# CPLD.net
KiCad netlist of a schematic drawn in Altium Designer
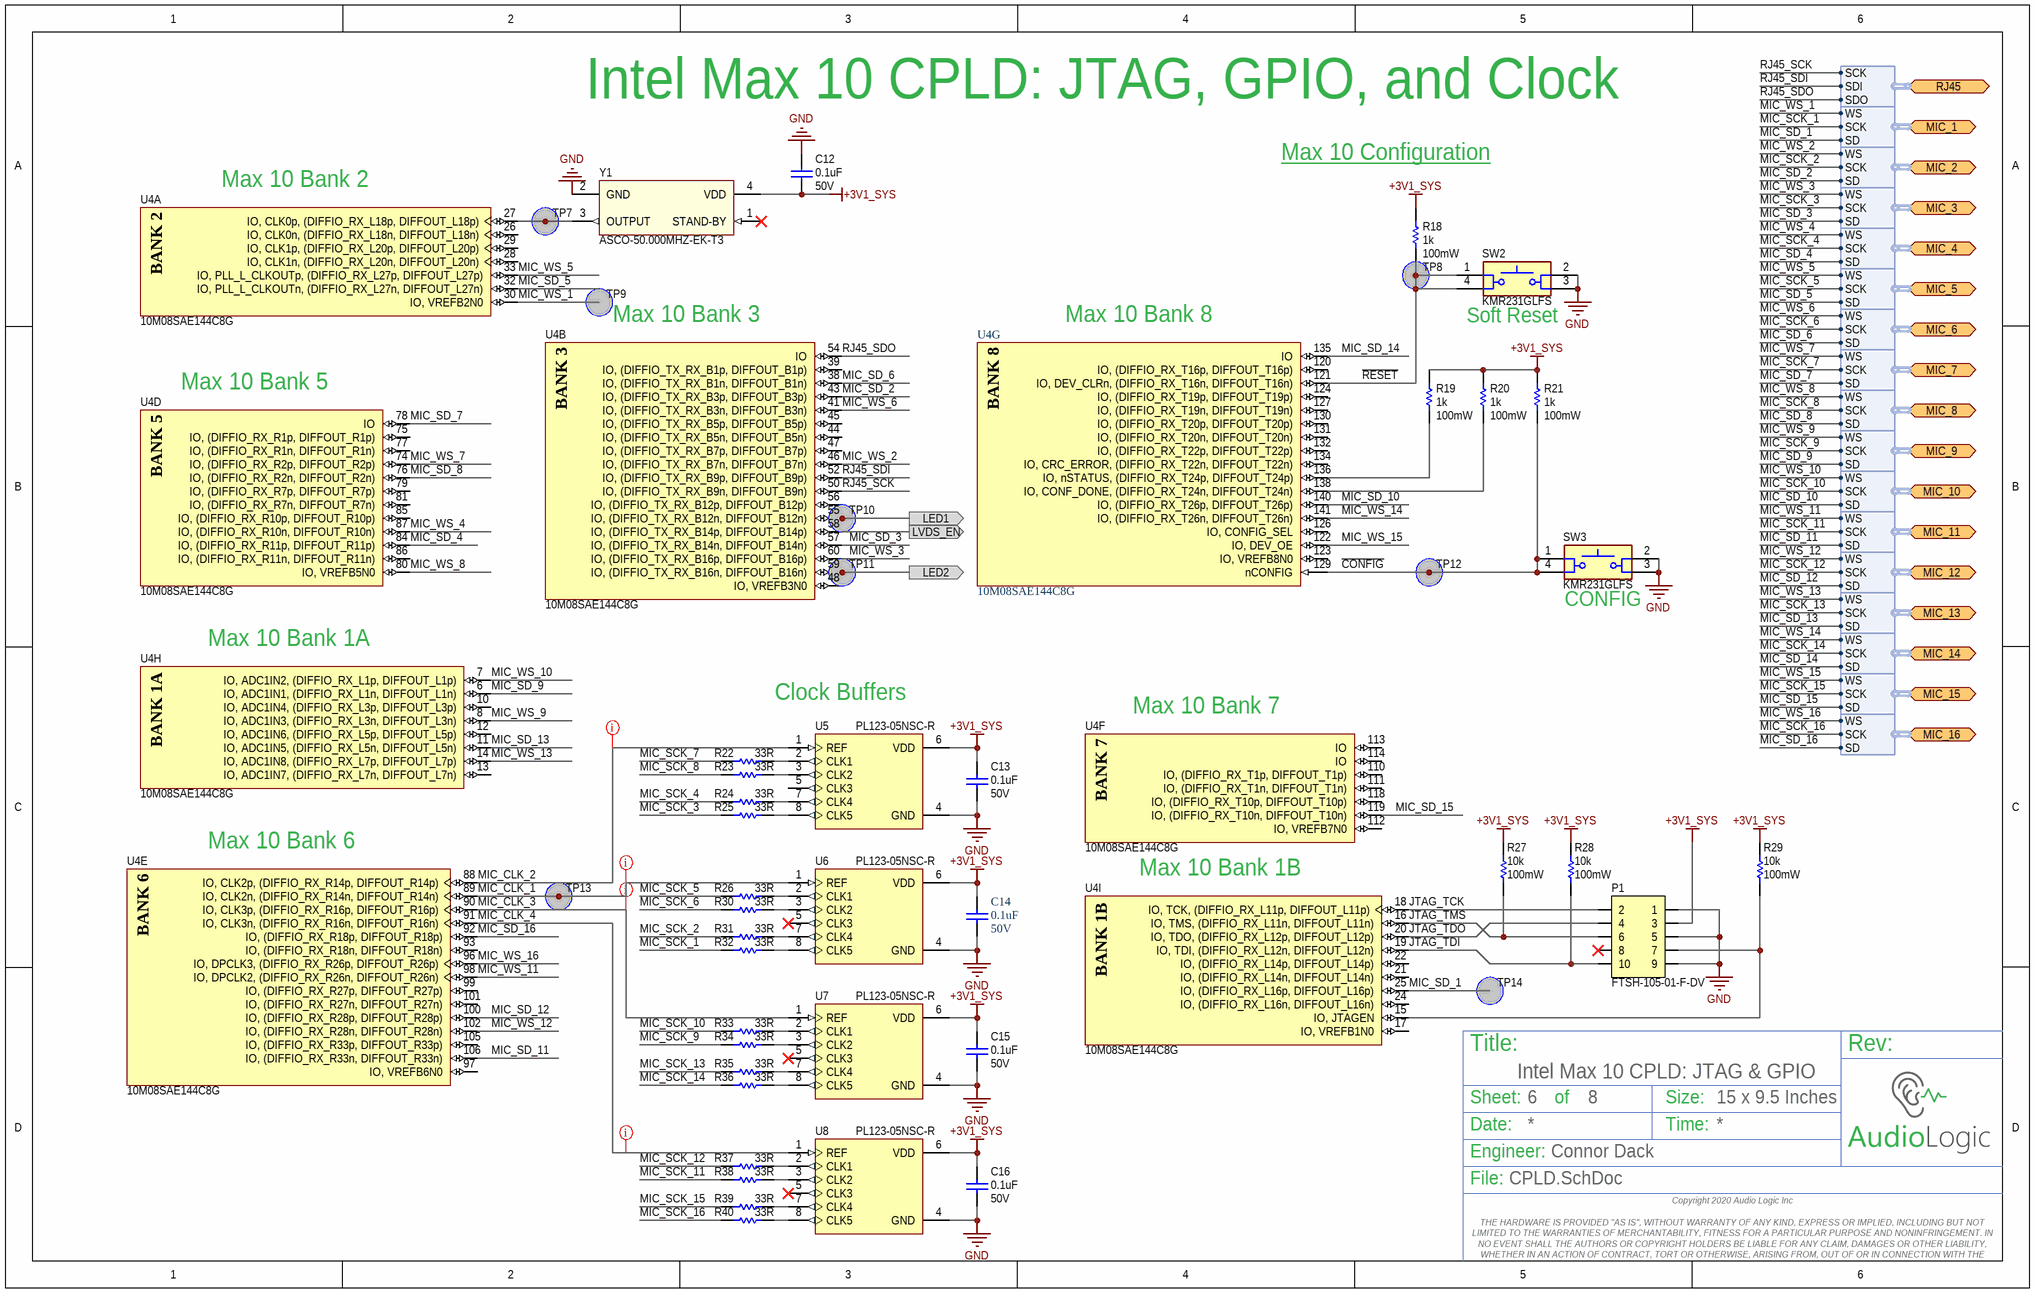
[diagram p0: CPLD.SchDoc]

(export (version "E")
  (design (tool "Eeschema 10.0.6"))
  (components
    (comp (ref "C12")
      (value "UMK105B7104KVHF")
      (footprint "2-0402_L")
      (description "CAP CER 0.1uF 50V X7R +/-10% 0402 AEC-Q200")
      (fields
        (field (name "MANUFACTURER") "Taiyo Yuden")
        (field (name "TOLERANCE") "10%")
        (field (name "CAPACITANCE") "0.1uF")
        (field (name "VOLTAGE RATING") "50V")
      )
      (libsource (lib "Schematic_Components") (part "UMK105B7104KVHF"))
    )
    (comp (ref "C13")
      (value "UMK105B7104KVHF")
      (footprint "2-0402_L")
      (description "CAP CER 0.1uF 50V X7R +/-10% 0402 AEC-Q200")
      (fields
        (field (name "MANUFACTURER") "Taiyo Yuden")
        (field (name "TOLERANCE") "10%")
        (field (name "CAPACITANCE") "0.1uF")
        (field (name "VOLTAGE RATING") "50V")
      )
      (libsource (lib "Schematic_Components") (part "UMK105B7104KVHF"))
    )
    (comp (ref "C14")
      (value "UMK105B7104KVHF")
      (footprint "2-0402_L")
      (description "CAP CER 0.1uF 50V X7R +/-10% 0402 AEC-Q200")
      (fields
        (field (name "MANUFACTURER") "Taiyo Yuden")
        (field (name "TOLERANCE") "10%")
        (field (name "CAPACITANCE") "0.1uF")
        (field (name "VOLTAGE RATING") "50V")
      )
      (libsource (lib "Schematic_Components") (part "UMK105B7104KVHF"))
    )
    (comp (ref "C15")
      (value "UMK105B7104KVHF")
      (footprint "2-0402_L")
      (description "CAP CER 0.1uF 50V X7R +/-10% 0402 AEC-Q200")
      (fields
        (field (name "MANUFACTURER") "Taiyo Yuden")
        (field (name "TOLERANCE") "10%")
        (field (name "CAPACITANCE") "0.1uF")
        (field (name "VOLTAGE RATING") "50V")
      )
      (libsource (lib "Schematic_Components") (part "UMK105B7104KVHF"))
    )
    (comp (ref "C16")
      (value "UMK105B7104KVHF")
      (footprint "2-0402_L")
      (description "CAP CER 0.1uF 50V X7R +/-10% 0402 AEC-Q200")
      (fields
        (field (name "MANUFACTURER") "Taiyo Yuden")
        (field (name "TOLERANCE") "10%")
        (field (name "CAPACITANCE") "0.1uF")
        (field (name "VOLTAGE RATING") "50V")
      )
      (libsource (lib "Schematic_Components") (part "UMK105B7104KVHF"))
    )
    (comp (ref "P1")
      (value "FTSH-105-01-F-DV")
      (footprint "HDR_2x5-SMD-1.27mm-K")
      (description "Pin Header 2x5, 1.27mm (50mil), SMD, Keying Shroud")
      (fields (field (name "MANUFACTURER") "Samtec"))
      (libsource (lib "Schematic_Components_CD") (part "CONN-2x5"))
    )
    (comp (ref "R18")
      (value "ERJ-2RKF1001X")
      (footprint "2-0402_R_L")
      (description "RES 1K OHM 1/10W 1% 0402 SMD")
      (fields
        (field (name "MANUFACTURER") "Panasonic Electronic Components")
        (field (name "TOLERANCE") "±1%")
        (field (name "POWER (WATTS)") "100mW")
        (field (name "RESISTANCE (OHMS)") "1k")
      )
      (libsource (lib "Schematic_Components") (part "ERJ-2RKF1001X"))
    )
    (comp (ref "R19")
      (value "ERJ-2RKF1001X")
      (footprint "2-0402_R_L")
      (description "RES 1K OHM 1/10W 1% 0402 SMD")
      (fields
        (field (name "MANUFACTURER") "Panasonic Electronic Components")
        (field (name "TOLERANCE") "±1%")
        (field (name "POWER (WATTS)") "100mW")
        (field (name "RESISTANCE (OHMS)") "1k")
      )
      (libsource (lib "Schematic_Components") (part "ERJ-2RKF1001X"))
    )
    (comp (ref "R20")
      (value "ERJ-2RKF1001X")
      (footprint "2-0402_R_L")
      (description "RES 1K OHM 1/10W 1% 0402 SMD")
      (fields
        (field (name "MANUFACTURER") "Panasonic Electronic Components")
        (field (name "TOLERANCE") "±1%")
        (field (name "POWER (WATTS)") "100mW")
        (field (name "RESISTANCE (OHMS)") "1k")
      )
      (libsource (lib "Schematic_Components") (part "ERJ-2RKF1001X"))
    )
    (comp (ref "R21")
      (value "ERJ-2RKF1001X")
      (footprint "2-0402_R_L")
      (description "RES 1K OHM 1/10W 1% 0402 SMD")
      (fields
        (field (name "MANUFACTURER") "Panasonic Electronic Components")
        (field (name "TOLERANCE") "±1%")
        (field (name "POWER (WATTS)") "100mW")
        (field (name "RESISTANCE (OHMS)") "1k")
      )
      (libsource (lib "Schematic_Components") (part "ERJ-2RKF1001X"))
    )
    (comp (ref "R22")
      (value "ERJ2RKF33R0X")
      (footprint "RESC1005X40X25LL05T05")
      (description "RES SMD 33 OHM 1% 1/10W 0402")
      (fields
        (field (name "MANUFACTURER") "Panasonic")
        (field (name "MANUFACTURER PART NUMBER") "ERJ-2RKF33R0X")
        (field (name "RESISTANCE") "33R")
      )
      (libsource (lib "Altium Content Vault") (part "RES"))
    )
    (comp (ref "R23")
      (value "ERJ2RKF33R0X")
      (footprint "RESC1005X40X25LL05T05")
      (description "RES SMD 33 OHM 1% 1/10W 0402")
      (fields
        (field (name "MANUFACTURER") "Panasonic")
        (field (name "MANUFACTURER PART NUMBER") "ERJ-2RKF33R0X")
        (field (name "RESISTANCE") "33R")
      )
      (libsource (lib "Altium Content Vault") (part "RES"))
    )
    (comp (ref "R24")
      (value "ERJ2RKF33R0X")
      (footprint "RESC1005X40X25LL05T05")
      (description "RES SMD 33 OHM 1% 1/10W 0402")
      (fields
        (field (name "MANUFACTURER") "Panasonic")
        (field (name "MANUFACTURER PART NUMBER") "ERJ-2RKF33R0X")
        (field (name "RESISTANCE") "33R")
      )
      (libsource (lib "Altium Content Vault") (part "RES"))
    )
    (comp (ref "R25")
      (value "ERJ2RKF33R0X")
      (footprint "RESC1005X40X25LL05T05")
      (description "RES SMD 33 OHM 1% 1/10W 0402")
      (fields
        (field (name "MANUFACTURER") "Panasonic")
        (field (name "MANUFACTURER PART NUMBER") "ERJ-2RKF33R0X")
        (field (name "RESISTANCE") "33R")
      )
      (libsource (lib "Altium Content Vault") (part "RES"))
    )
    (comp (ref "R26")
      (value "ERJ2RKF33R0X")
      (footprint "RESC1005X40X25LL05T05")
      (description "RES SMD 33 OHM 1% 1/10W 0402")
      (fields
        (field (name "MANUFACTURER") "Panasonic")
        (field (name "MANUFACTURER PART NUMBER") "ERJ-2RKF33R0X")
        (field (name "RESISTANCE") "33R")
      )
      (libsource (lib "Altium Content Vault") (part "RES"))
    )
    (comp (ref "R27")
      (value "ERJ-2RKF1002X")
      (footprint "2-0402_R_L")
      (description "RES 10K OHM 1/10W 1% 0402 SMD")
      (fields
        (field (name "MANUFACTURER") "Panasonic Electronic Components")
        (field (name "TOLERANCE") "±1%")
        (field (name "POWER (WATTS)") "100mW")
        (field (name "RESISTANCE (OHMS)") "10k")
      )
      (libsource (lib "Schematic_Components") (part "ERJ-2RKF1002X"))
    )
    (comp (ref "R28")
      (value "ERJ-2RKF1002X")
      (footprint "2-0402_R_L")
      (description "RES 10K OHM 1/10W 1% 0402 SMD")
      (fields
        (field (name "MANUFACTURER") "Panasonic Electronic Components")
        (field (name "TOLERANCE") "±1%")
        (field (name "POWER (WATTS)") "100mW")
        (field (name "RESISTANCE (OHMS)") "10k")
      )
      (libsource (lib "Schematic_Components") (part "ERJ-2RKF1002X"))
    )
    (comp (ref "R29")
      (value "ERJ-2RKF1002X")
      (footprint "2-0402_R_L")
      (description "RES 10K OHM 1/10W 1% 0402 SMD")
      (fields
        (field (name "MANUFACTURER") "Panasonic Electronic Components")
        (field (name "TOLERANCE") "±1%")
        (field (name "POWER (WATTS)") "100mW")
        (field (name "RESISTANCE (OHMS)") "10k")
      )
      (libsource (lib "Schematic_Components") (part "ERJ-2RKF1002X"))
    )
    (comp (ref "R30")
      (value "ERJ2RKF33R0X")
      (footprint "RESC1005X40X25LL05T05")
      (description "RES SMD 33 OHM 1% 1/10W 0402")
      (fields
        (field (name "MANUFACTURER") "Panasonic")
        (field (name "MANUFACTURER PART NUMBER") "ERJ-2RKF33R0X")
        (field (name "RESISTANCE") "33R")
      )
      (libsource (lib "Altium Content Vault") (part "RES"))
    )
    (comp (ref "R31")
      (value "ERJ2RKF33R0X")
      (footprint "RESC1005X40X25LL05T05")
      (description "RES SMD 33 OHM 1% 1/10W 0402")
      (fields
        (field (name "MANUFACTURER") "Panasonic")
        (field (name "MANUFACTURER PART NUMBER") "ERJ-2RKF33R0X")
        (field (name "RESISTANCE") "33R")
      )
      (libsource (lib "Altium Content Vault") (part "RES"))
    )
    (comp (ref "R32")
      (value "ERJ2RKF33R0X")
      (footprint "RESC1005X40X25LL05T05")
      (description "RES SMD 33 OHM 1% 1/10W 0402")
      (fields
        (field (name "MANUFACTURER") "Panasonic")
        (field (name "MANUFACTURER PART NUMBER") "ERJ-2RKF33R0X")
        (field (name "RESISTANCE") "33R")
      )
      (libsource (lib "Altium Content Vault") (part "RES"))
    )
    (comp (ref "R33")
      (value "ERJ2RKF33R0X")
      (footprint "RESC1005X40X25LL05T05")
      (description "RES SMD 33 OHM 1% 1/10W 0402")
      (fields
        (field (name "MANUFACTURER") "Panasonic")
        (field (name "MANUFACTURER PART NUMBER") "ERJ-2RKF33R0X")
        (field (name "RESISTANCE") "33R")
      )
      (libsource (lib "Altium Content Vault") (part "RES"))
    )
    (comp (ref "R34")
      (value "ERJ2RKF33R0X")
      (footprint "RESC1005X40X25LL05T05")
      (description "RES SMD 33 OHM 1% 1/10W 0402")
      (fields
        (field (name "MANUFACTURER") "Panasonic")
        (field (name "MANUFACTURER PART NUMBER") "ERJ-2RKF33R0X")
        (field (name "RESISTANCE") "33R")
      )
      (libsource (lib "Altium Content Vault") (part "RES"))
    )
    (comp (ref "R35")
      (value "ERJ2RKF33R0X")
      (footprint "RESC1005X40X25LL05T05")
      (description "RES SMD 33 OHM 1% 1/10W 0402")
      (fields
        (field (name "MANUFACTURER") "Panasonic")
        (field (name "MANUFACTURER PART NUMBER") "ERJ-2RKF33R0X")
        (field (name "RESISTANCE") "33R")
      )
      (libsource (lib "Altium Content Vault") (part "RES"))
    )
    (comp (ref "R36")
      (value "ERJ2RKF33R0X")
      (footprint "RESC1005X40X25LL05T05")
      (description "RES SMD 33 OHM 1% 1/10W 0402")
      (fields
        (field (name "MANUFACTURER") "Panasonic")
        (field (name "MANUFACTURER PART NUMBER") "ERJ-2RKF33R0X")
        (field (name "RESISTANCE") "33R")
      )
      (libsource (lib "Altium Content Vault") (part "RES"))
    )
    (comp (ref "R37")
      (value "ERJ2RKF33R0X")
      (footprint "RESC1005X40X25LL05T05")
      (description "RES SMD 33 OHM 1% 1/10W 0402")
      (fields
        (field (name "MANUFACTURER") "Panasonic")
        (field (name "MANUFACTURER PART NUMBER") "ERJ-2RKF33R0X")
        (field (name "RESISTANCE") "33R")
      )
      (libsource (lib "Altium Content Vault") (part "RES"))
    )
    (comp (ref "R38")
      (value "ERJ2RKF33R0X")
      (footprint "RESC1005X40X25LL05T05")
      (description "RES SMD 33 OHM 1% 1/10W 0402")
      (fields
        (field (name "MANUFACTURER") "Panasonic")
        (field (name "MANUFACTURER PART NUMBER") "ERJ-2RKF33R0X")
        (field (name "RESISTANCE") "33R")
      )
      (libsource (lib "Altium Content Vault") (part "RES"))
    )
    (comp (ref "R39")
      (value "ERJ2RKF33R0X")
      (footprint "RESC1005X40X25LL05T05")
      (description "RES SMD 33 OHM 1% 1/10W 0402")
      (fields
        (field (name "MANUFACTURER") "Panasonic")
        (field (name "MANUFACTURER PART NUMBER") "ERJ-2RKF33R0X")
        (field (name "RESISTANCE") "33R")
      )
      (libsource (lib "Altium Content Vault") (part "RES"))
    )
    (comp (ref "R40")
      (value "ERJ2RKF33R0X")
      (footprint "RESC1005X40X25LL05T05")
      (description "RES SMD 33 OHM 1% 1/10W 0402")
      (fields
        (field (name "MANUFACTURER") "Panasonic")
        (field (name "MANUFACTURER PART NUMBER") "ERJ-2RKF33R0X")
        (field (name "RESISTANCE") "33R")
      )
      (libsource (lib "Altium Content Vault") (part "RES"))
    )
    (comp (ref "SW2")
      (value "SPST-NO")
      (footprint "CKCP-KMR231GLFS")
      (description "SWITCH TACTILE SPST-NO 0.05A 32V")
      (fields (field (name "MANUFACTURER") "ITT C&K") (field (name "MANUFACTURER PART NUMBER") "KMR231GLFS"))
      (libsource (lib "Schematic_Components") (part "SW-SPST-NO_KMR231GLFS"))
    )
    (comp (ref "SW3")
      (value "SPST-NO")
      (footprint "CKCP-KMR231GLFS")
      (description "SWITCH TACTILE SPST-NO 0.05A 32V")
      (fields (field (name "MANUFACTURER") "ITT C&K") (field (name "MANUFACTURER PART NUMBER") "KMR231GLFS"))
      (libsource (lib "Schematic_Components") (part "SW-SPST-NO_KMR231GLFS"))
    )
    (comp (ref "TP7")
      (value "Testpoint")
      (footprint "Testpoint_SMT")
      (description "Testpoint, 1-Pin, SMT")
      (libsource (lib "Schematic_Components") (part "Testpoint_SMT"))
    )
    (comp (ref "TP8")
      (value "Testpoint")
      (footprint "Testpoint_SMT")
      (description "Testpoint, 1-Pin, SMT")
      (libsource (lib "Schematic_Components") (part "Testpoint_SMT"))
    )
    (comp (ref "TP9")
      (value "Testpoint")
      (footprint "Testpoint_SMT")
      (description "Testpoint, 1-Pin, SMT")
      (libsource (lib "Schematic_Components") (part "Testpoint_SMT"))
    )
    (comp (ref "TP10")
      (value "Testpoint")
      (footprint "Testpoint_SMT")
      (description "Testpoint, 1-Pin, SMT")
      (libsource (lib "Schematic_Components") (part "Testpoint_SMT"))
    )
    (comp (ref "TP11")
      (value "Testpoint")
      (footprint "Testpoint_SMT")
      (description "Testpoint, 1-Pin, SMT")
      (libsource (lib "Schematic_Components") (part "Testpoint_SMT"))
    )
    (comp (ref "TP12")
      (value "Testpoint")
      (footprint "Testpoint_SMT")
      (description "Testpoint, 1-Pin, SMT")
      (libsource (lib "Schematic_Components") (part "Testpoint_SMT"))
    )
    (comp (ref "TP13")
      (value "Testpoint")
      (footprint "Testpoint_SMT")
      (description "Testpoint, 1-Pin, SMT")
      (libsource (lib "Schematic_Components") (part "Testpoint_SMT"))
    )
    (comp (ref "TP14")
      (value "Testpoint")
      (footprint "Testpoint_SMT")
      (description "Testpoint, 1-Pin, SMT")
      (libsource (lib "Schematic_Components") (part "Testpoint_SMT"))
    )
    (comp (ref "U4")
      (value "10M08SAE144C8G")
      (footprint "ALTR-EQFP144_A165_D2-500_M")
      (fields (field (name "MANUFACTURER") "Altera"))
      (libsource (lib "Schematic_Components_CD") (part "10M08SAE144C8G"))
    )
    (comp (ref "U5")
      (value "PL123-05NSC-R")
      (footprint "SOP127P600X175-8N")
      (description "IC CLK BUFFER 1:5 134MHZ 8SOP")
      (fields (field (name "MANUFACTURER") "Microchip"))
      (libsource (lib "Schematic_Components_CD") (part "PL123-05NSC-R"))
    )
    (comp (ref "U6")
      (value "PL123-05NSC-R")
      (footprint "SOP127P600X175-8N")
      (description "IC CLK BUFFER 1:5 134MHZ 8SOP")
      (fields (field (name "MANUFACTURER") "Microchip"))
      (libsource (lib "Schematic_Components_CD") (part "PL123-05NSC-R"))
    )
    (comp (ref "U7")
      (value "PL123-05NSC-R")
      (footprint "SOP127P600X175-8N")
      (description "IC CLK BUFFER 1:5 134MHZ 8SOP")
      (fields (field (name "MANUFACTURER") "Microchip"))
      (libsource (lib "Schematic_Components_CD") (part "PL123-05NSC-R"))
    )
    (comp (ref "U8")
      (value "PL123-05NSC-R")
      (footprint "SOP127P600X175-8N")
      (description "IC CLK BUFFER 1:5 134MHZ 8SOP")
      (fields (field (name "MANUFACTURER") "Microchip"))
      (libsource (lib "Schematic_Components_CD") (part "PL123-05NSC-R"))
    )
    (comp (ref "Y1")
      (value "ASCO-50.000MHZ-EK-T3")
      (footprint "ABRA-ASCO-50.000MHZ-EK-T3-4_V")
      (description "Crystal Clock Oscillator, 50 MHz, -20 to 70 degC, 1.6 x 1.2 x 0.7 mm SMD")
      (fields (field (name "MANUFACTURER") "Abracon"))
      (libsource (lib "Altium Content Vault") (part "ABRA-ASCO-50_000MHZ-EK-T3-4"))
    )
  )
  (nets
    (net (code "18") (name "+3V1_SYS") (class "Default")
      (node (ref "C12") (pin "2") (pinfunction "2_2") (pintype "passive"))
      (node (ref "C13") (pin "2") (pinfunction "2_2") (pintype "passive"))
      (node (ref "C14") (pin "2") (pinfunction "2_2") (pintype "passive"))
      (node (ref "C15") (pin "2") (pinfunction "2_2") (pintype "passive"))
      (node (ref "C16") (pin "2") (pinfunction "2_2") (pintype "passive"))
      (node (ref "P1") (pin "3") (pinfunction "3_3") (pintype "passive"))
      (node (ref "R18") (pin "2") (pinfunction "2_2") (pintype "passive"))
      (node (ref "R19") (pin "2") (pinfunction "2_2") (pintype "passive"))
      (node (ref "R20") (pin "2") (pinfunction "2_2") (pintype "passive"))
      (node (ref "R21") (pin "2") (pinfunction "2_2") (pintype "passive"))
      (node (ref "R27") (pin "2") (pinfunction "2_2") (pintype "passive"))
      (node (ref "R28") (pin "2") (pinfunction "2_2") (pintype "passive"))
      (node (ref "R29") (pin "2") (pinfunction "2_2") (pintype "passive"))
      (node (ref "U5") (pin "6") (pinfunction "VDD_6") (pintype "power_in"))
      (node (ref "U6") (pin "6") (pinfunction "VDD_6") (pintype "power_in"))
      (node (ref "U7") (pin "6") (pinfunction "VDD_6") (pintype "power_in"))
      (node (ref "U8") (pin "6") (pinfunction "VDD_6") (pintype "power_in"))
      (node (ref "Y1") (pin "4") (pinfunction "VDD_4") (pintype "power_in"))
    )
    (net (code "19") (name "/CONFIG") (class "Default")
      (node (ref "R21") (pin "1") (pinfunction "1_1") (pintype "passive"))
      (node (ref "SW3") (pin "1") (pinfunction "1_1") (pintype "passive"))
      (node (ref "SW3") (pin "4") (pinfunction "4_4") (pintype "passive"))
      (node (ref "TP12") (pin "1") (pinfunction "1_1") (pintype "passive"))
      (node (ref "U4") (pin "129") (pinfunction "nCONFIG_129") (pintype "input"))
    )
    (net (code "20") (name "/JTAG_TCK") (class "Default")
      (node (ref "P1") (pin "2") (pinfunction "2_2") (pintype "passive"))
      (node (ref "U4") (pin "18") (pinfunction "IO,_TCK,_(DIFFIO_RX_L11p,_DIFFOUT_L11p)_18") (pintype "bidirectional"))
    )
    (net (code "21") (name "/JTAG_TDI") (class "Default")
      (node (ref "P1") (pin "10") (pinfunction "10_10") (pintype "passive"))
      (node (ref "R28") (pin "1") (pinfunction "1_1") (pintype "passive"))
      (node (ref "U4") (pin "19") (pinfunction "IO,_TDI,_(DIFFIO_RX_L12n,_DIFFOUT_L12n)_19") (pintype "bidirectional"))
    )
    (net (code "22") (name "/JTAG_TDO") (class "Default")
      (node (ref "P1") (pin "4") (pinfunction "4_4") (pintype "passive"))
      (node (ref "U4") (pin "20") (pinfunction "IO,_TDO,_(DIFFIO_RX_L12p,_DIFFOUT_L12p)_20") (pintype "bidirectional"))
    )
    (net (code "23") (name "/JTAG_TMS") (class "Default")
      (node (ref "P1") (pin "6") (pinfunction "6_6") (pintype "passive"))
      (node (ref "R27") (pin "1") (pinfunction "1_1") (pintype "passive"))
      (node (ref "U4") (pin "16") (pinfunction "IO,_TMS,_(DIFFIO_RX_L11n,_DIFFOUT_L11n)_16") (pintype "bidirectional"))
    )
    (net (code "24") (name "/LED1") (class "Default")
      (node (ref "TP10") (pin "1") (pinfunction "1_1") (pintype "passive"))
      (node (ref "U4") (pin "55") (pinfunction "IO,_(DIFFIO_TX_RX_B12n,_DIFFOUT_B12n)_55") (pintype "bidirectional"))
    )
    (net (code "25") (name "/LED2") (class "Default")
      (node (ref "TP11") (pin "1") (pinfunction "1_1") (pintype "passive"))
      (node (ref "U4") (pin "59") (pinfunction "IO,_(DIFFIO_TX_RX_B16n,_DIFFOUT_B16n)_59") (pintype "bidirectional"))
    )
    (net (code "26") (name "/LVDS_EN") (class "Default")
      (node (ref "U4") (pin "58") (pinfunction "IO,_(DIFFIO_TX_RX_B14p,_DIFFOUT_B14p)_58") (pintype "bidirectional"))
    )
    (net (code "30") (name "/MIC_CLK_1") (class "Default")
      (node (ref "TP13") (pin "1") (pinfunction "1_1") (pintype "passive"))
      (node (ref "U4") (pin "89") (pinfunction "IO,_CLK2n,_(DIFFIO_RX_R14n,_DIFFOUT_R14n)_89") (pintype "bidirectional"))
      (node (ref "U6") (pin "1") (pinfunction "REF_1") (pintype "input"))
    )
    (net (code "31") (name "/MIC_CLK_2") (class "Default")
      (node (ref "U4") (pin "88") (pinfunction "IO,_CLK2p,_(DIFFIO_RX_R14p,_DIFFOUT_R14p)_88") (pintype "bidirectional"))
      (node (ref "U5") (pin "1") (pinfunction "REF_1") (pintype "input"))
    )
    (net (code "32") (name "/MIC_CLK_3") (class "Default")
      (node (ref "U4") (pin "90") (pinfunction "IO,_CLK3p,_(DIFFIO_RX_R16p,_DIFFOUT_R16p)_90") (pintype "bidirectional"))
      (node (ref "U7") (pin "1") (pinfunction "REF_1") (pintype "input"))
    )
    (net (code "33") (name "/MIC_CLK_4") (class "Default")
      (node (ref "U4") (pin "91") (pinfunction "IO,_CLK3n,_(DIFFIO_RX_R16n,_DIFFOUT_R16n)_91") (pintype "bidirectional"))
      (node (ref "U8") (pin "1") (pinfunction "REF_1") (pintype "input"))
    )
    (net (code "34") (name "/MIC_SCK_1") (class "Default")
      (node (ref "R32") (pin "1") (pinfunction "1_1") (pintype "passive"))
    )
    (net (code "35") (name "/MIC_SCK_2") (class "Default")
      (node (ref "R31") (pin "1") (pinfunction "1_1") (pintype "passive"))
    )
    (net (code "36") (name "/MIC_SCK_3") (class "Default")
      (node (ref "R25") (pin "1") (pinfunction "1_1") (pintype "passive"))
    )
    (net (code "37") (name "/MIC_SCK_4") (class "Default")
      (node (ref "R24") (pin "1") (pinfunction "1_1") (pintype "passive"))
    )
    (net (code "38") (name "/MIC_SCK_5") (class "Default")
      (node (ref "R26") (pin "1") (pinfunction "1_1") (pintype "passive"))
    )
    (net (code "39") (name "/MIC_SCK_6") (class "Default")
      (node (ref "R30") (pin "1") (pinfunction "1_1") (pintype "passive"))
    )
    (net (code "40") (name "/MIC_SCK_7") (class "Default")
      (node (ref "R22") (pin "1") (pinfunction "1_1") (pintype "passive"))
    )
    (net (code "41") (name "/MIC_SCK_8") (class "Default")
      (node (ref "R23") (pin "1") (pinfunction "1_1") (pintype "passive"))
    )
    (net (code "42") (name "/MIC_SCK_9") (class "Default")
      (node (ref "R34") (pin "1") (pinfunction "1_1") (pintype "passive"))
    )
    (net (code "43") (name "/MIC_SCK_10") (class "Default")
      (node (ref "R33") (pin "1") (pinfunction "1_1") (pintype "passive"))
    )
    (net (code "44") (name "/MIC_SCK_11") (class "Default")
      (node (ref "R38") (pin "1") (pinfunction "1_1") (pintype "passive"))
    )
    (net (code "45") (name "/MIC_SCK_12") (class "Default")
      (node (ref "R37") (pin "1") (pinfunction "1_1") (pintype "passive"))
    )
    (net (code "46") (name "/MIC_SCK_13") (class "Default")
      (node (ref "R35") (pin "1") (pinfunction "1_1") (pintype "passive"))
    )
    (net (code "47") (name "/MIC_SCK_14") (class "Default")
      (node (ref "R36") (pin "1") (pinfunction "1_1") (pintype "passive"))
    )
    (net (code "48") (name "/MIC_SCK_15") (class "Default")
      (node (ref "R39") (pin "1") (pinfunction "1_1") (pintype "passive"))
    )
    (net (code "49") (name "/MIC_SCK_16") (class "Default")
      (node (ref "R40") (pin "1") (pinfunction "1_1") (pintype "passive"))
    )
    (net (code "50") (name "/MIC_SD_1") (class "Default")
      (node (ref "TP14") (pin "1") (pinfunction "1_1") (pintype "passive"))
      (node (ref "U4") (pin "25") (pinfunction "IO,_(DIFFIO_RX_L16p,_DIFFOUT_L16p)_25") (pintype "bidirectional"))
    )
    (net (code "51") (name "/MIC_SD_2") (class "Default")
      (node (ref "U4") (pin "43") (pinfunction "IO,_(DIFFIO_TX_RX_B3p,_DIFFOUT_B3p)_43") (pintype "bidirectional"))
    )
    (net (code "52") (name "/MIC_SD_3") (class "Default")
      (node (ref "U4") (pin "57") (pinfunction "IO,_(DIFFIO_TX_RX_B14n,_DIFFOUT_B14n)_57") (pintype "bidirectional"))
    )
    (net (code "53") (name "/MIC_SD_4") (class "Default")
      (node (ref "U4") (pin "84") (pinfunction "IO,_(DIFFIO_RX_R11p,_DIFFOUT_R11p)_84") (pintype "bidirectional"))
    )
    (net (code "54") (name "/MIC_SD_5") (class "Default")
      (node (ref "U4") (pin "32") (pinfunction "IO,_PLL_L_CLKOUTn,_(DIFFIO_RX_L27n,_DIFFOUT_L27n)_32") (pintype "bidirectional"))
    )
    (net (code "55") (name "/MIC_SD_6") (class "Default")
      (node (ref "U4") (pin "38") (pinfunction "IO,_(DIFFIO_TX_RX_B1n,_DIFFOUT_B1n)_38") (pintype "bidirectional"))
    )
    (net (code "56") (name "/MIC_SD_7") (class "Default")
      (node (ref "U4") (pin "78") (pinfunction "IO_78") (pintype "bidirectional"))
    )
    (net (code "57") (name "/MIC_SD_8") (class "Default")
      (node (ref "U4") (pin "76") (pinfunction "IO,_(DIFFIO_RX_R2n,_DIFFOUT_R2n)_76") (pintype "bidirectional"))
    )
    (net (code "58") (name "/MIC_SD_9") (class "Default")
      (node (ref "U4") (pin "6") (pinfunction "IO,_ADC1IN1,_(DIFFIO_RX_L1n,_DIFFOUT_L1n)_6") (pintype "bidirectional"))
    )
    (net (code "59") (name "/MIC_SD_10") (class "Default")
      (node (ref "U4") (pin "140") (pinfunction "IO,_(DIFFIO_RX_T26p,_DIFFOUT_T26p)_140") (pintype "bidirectional"))
    )
    (net (code "60") (name "/MIC_SD_11") (class "Default")
      (node (ref "U4") (pin "106") (pinfunction "IO,_(DIFFIO_RX_R33n,_DIFFOUT_R33n)_106") (pintype "bidirectional"))
    )
    (net (code "61") (name "/MIC_SD_12") (class "Default")
      (node (ref "U4") (pin "100") (pinfunction "IO,_(DIFFIO_RX_R28p,_DIFFOUT_R28p)_100") (pintype "bidirectional"))
    )
    (net (code "62") (name "/MIC_SD_13") (class "Default")
      (node (ref "U4") (pin "11") (pinfunction "IO,_ADC1IN5,_(DIFFIO_RX_L5n,_DIFFOUT_L5n)_11") (pintype "bidirectional"))
    )
    (net (code "63") (name "/MIC_SD_14") (class "Default")
      (node (ref "U4") (pin "135") (pinfunction "IO_135") (pintype "bidirectional"))
    )
    (net (code "64") (name "/MIC_SD_15") (class "Default")
      (node (ref "U4") (pin "119") (pinfunction "IO,_(DIFFIO_RX_T10n,_DIFFOUT_T10n)_119") (pintype "bidirectional"))
    )
    (net (code "65") (name "/MIC_SD_16") (class "Default")
      (node (ref "U4") (pin "92") (pinfunction "IO,_(DIFFIO_RX_R18p,_DIFFOUT_R18p)_92") (pintype "bidirectional"))
    )
    (net (code "66") (name "/MIC_WS_1") (class "Default")
      (node (ref "TP9") (pin "1") (pinfunction "1_1") (pintype "passive"))
      (node (ref "U4") (pin "30") (pinfunction "IO,_VREFB2N0_30") (pintype "bidirectional"))
    )
    (net (code "67") (name "/MIC_WS_2") (class "Default")
      (node (ref "U4") (pin "46") (pinfunction "IO,_(DIFFIO_TX_RX_B7n,_DIFFOUT_B7n)_46") (pintype "bidirectional"))
    )
    (net (code "68") (name "/MIC_WS_3") (class "Default")
      (node (ref "U4") (pin "60") (pinfunction "IO,_(DIFFIO_TX_RX_B16p,_DIFFOUT_B16p)_60") (pintype "bidirectional"))
    )
    (net (code "69") (name "/MIC_WS_4") (class "Default")
      (node (ref "U4") (pin "87") (pinfunction "IO,_(DIFFIO_RX_R10n,_DIFFOUT_R10n)_87") (pintype "bidirectional"))
    )
    (net (code "70") (name "/MIC_WS_5") (class "Default")
      (node (ref "U4") (pin "33") (pinfunction "IO,_PLL_L_CLKOUTp,_(DIFFIO_RX_L27p,_DIFFOUT_L27p)_33") (pintype "bidirectional"))
    )
    (net (code "71") (name "/MIC_WS_6") (class "Default")
      (node (ref "U4") (pin "41") (pinfunction "IO,_(DIFFIO_TX_RX_B3n,_DIFFOUT_B3n)_41") (pintype "bidirectional"))
    )
    (net (code "72") (name "/MIC_WS_7") (class "Default")
      (node (ref "U4") (pin "74") (pinfunction "IO,_(DIFFIO_RX_R2p,_DIFFOUT_R2p)_74") (pintype "bidirectional"))
    )
    (net (code "73") (name "/MIC_WS_8") (class "Default")
      (node (ref "U4") (pin "80") (pinfunction "IO,_VREFB5N0_80") (pintype "bidirectional"))
    )
    (net (code "74") (name "/MIC_WS_9") (class "Default")
      (node (ref "U4") (pin "8") (pinfunction "IO,_ADC1IN3,_(DIFFIO_RX_L3n,_DIFFOUT_L3n)_8") (pintype "bidirectional"))
    )
    (net (code "75") (name "/MIC_WS_10") (class "Default")
      (node (ref "U4") (pin "7") (pinfunction "IO,_ADC1IN2,_(DIFFIO_RX_L1p,_DIFFOUT_L1p)_7") (pintype "bidirectional"))
    )
    (net (code "76") (name "/MIC_WS_11") (class "Default")
      (node (ref "U4") (pin "98") (pinfunction "IO,_DPCLK2,_(DIFFIO_RX_R26n,_DIFFOUT_R26n)_98") (pintype "bidirectional"))
    )
    (net (code "77") (name "/MIC_WS_12") (class "Default")
      (node (ref "U4") (pin "102") (pinfunction "IO,_(DIFFIO_RX_R28n,_DIFFOUT_R28n)_102") (pintype "bidirectional"))
    )
    (net (code "78") (name "/MIC_WS_13") (class "Default")
      (node (ref "U4") (pin "14") (pinfunction "IO,_ADC1IN8,_(DIFFIO_RX_L7p,_DIFFOUT_L7p)_14") (pintype "bidirectional"))
    )
    (net (code "79") (name "/MIC_WS_14") (class "Default")
      (node (ref "U4") (pin "141") (pinfunction "IO,_(DIFFIO_RX_T26n,_DIFFOUT_T26n)_141") (pintype "bidirectional"))
    )
    (net (code "80") (name "/MIC_WS_15") (class "Default")
      (node (ref "U4") (pin "122") (pinfunction "IO,_DEV_OE_122") (pintype "bidirectional"))
    )
    (net (code "81") (name "/MIC_WS_16") (class "Default")
      (node (ref "U4") (pin "96") (pinfunction "IO,_DPCLK3,_(DIFFIO_RX_R26p,_DIFFOUT_R26p)_96") (pintype "bidirectional"))
    )
    (net (code "82") (name "/RESET") (class "Default")
      (node (ref "R18") (pin "1") (pinfunction "1_1") (pintype "passive"))
      (node (ref "SW2") (pin "1") (pinfunction "1_1") (pintype "passive"))
      (node (ref "SW2") (pin "4") (pinfunction "4_4") (pintype "passive"))
      (node (ref "TP8") (pin "1") (pinfunction "1_1") (pintype "passive"))
      (node (ref "U4") (pin "121") (pinfunction "IO,_DEV_CLRn,_(DIFFIO_RX_T16n,_DIFFOUT_T16n)_121") (pintype "bidirectional"))
    )
    (net (code "83") (name "/RJ45_SCK") (class "Default")
      (node (ref "U4") (pin "50") (pinfunction "IO,_(DIFFIO_TX_RX_B9n,_DIFFOUT_B9n)_50") (pintype "bidirectional"))
    )
    (net (code "84") (name "/RJ45_SDI") (class "Default")
      (node (ref "U4") (pin "52") (pinfunction "IO,_(DIFFIO_TX_RX_B9p,_DIFFOUT_B9p)_52") (pintype "bidirectional"))
    )
    (net (code "85") (name "/RJ45_SDO") (class "Default")
      (node (ref "U4") (pin "54") (pinfunction "IO_54") (pintype "bidirectional"))
    )
    (net (code "100") (name "GND") (class "Default")
      (node (ref "C12") (pin "1") (pinfunction "1_1") (pintype "passive"))
      (node (ref "C13") (pin "1") (pinfunction "1_1") (pintype "passive"))
      (node (ref "C14") (pin "1") (pinfunction "1_1") (pintype "passive"))
      (node (ref "C15") (pin "1") (pinfunction "1_1") (pintype "passive"))
      (node (ref "C16") (pin "1") (pinfunction "1_1") (pintype "passive"))
      (node (ref "P1") (pin "1") (pinfunction "1_1") (pintype "passive"))
      (node (ref "P1") (pin "5") (pinfunction "5_5") (pintype "passive"))
      (node (ref "P1") (pin "9") (pinfunction "9_9") (pintype "passive"))
      (node (ref "SW2") (pin "2") (pinfunction "2_2") (pintype "passive"))
      (node (ref "SW2") (pin "3") (pinfunction "3_3") (pintype "passive"))
      (node (ref "SW3") (pin "2") (pinfunction "2_2") (pintype "passive"))
      (node (ref "SW3") (pin "3") (pinfunction "3_3") (pintype "passive"))
      (node (ref "U5") (pin "4") (pinfunction "GND_4") (pintype "power_in"))
      (node (ref "U6") (pin "4") (pinfunction "GND_4") (pintype "power_in"))
      (node (ref "U7") (pin "4") (pinfunction "GND_4") (pintype "power_in"))
      (node (ref "U8") (pin "4") (pinfunction "GND_4") (pintype "power_in"))
      (node (ref "Y1") (pin "2") (pinfunction "GND_2") (pintype "power_in"))
    )
    (net (code "101") (name "Net-(U4A-IO,_CLK0p,_(DIFFIO_RX_L18p,_DIFFOUT_L18p))") (class "Default")
      (node (ref "TP7") (pin "1") (pinfunction "1_1") (pintype "passive"))
      (node (ref "U4") (pin "27") (pinfunction "IO,_CLK0p,_(DIFFIO_RX_L18p,_DIFFOUT_L18p)_27") (pintype "bidirectional"))
      (node (ref "Y1") (pin "3") (pinfunction "OUTPUT_3") (pintype "output"))
    )
    (net (code "102") (name "Net-(U4G-IO,_CONF_DONE,_(DIFFIO_RX_T24n,_DIFFOUT_T24n))") (class "Default")
      (node (ref "R20") (pin "1") (pinfunction "1_1") (pintype "passive"))
      (node (ref "U4") (pin "138") (pinfunction "IO,_CONF_DONE,_(DIFFIO_RX_T24n,_DIFFOUT_T24n)_138") (pintype "bidirectional"))
    )
    (net (code "103") (name "Net-(U4G-IO,_nSTATUS,_(DIFFIO_RX_T24p,_DIFFOUT_T24p))") (class "Default")
      (node (ref "R19") (pin "1") (pinfunction "1_1") (pintype "passive"))
      (node (ref "U4") (pin "136") (pinfunction "IO,_nSTATUS,_(DIFFIO_RX_T24p,_DIFFOUT_T24p)_136") (pintype "bidirectional"))
    )
    (net (code "104") (name "Net-(U4I-IO,_JTAGEN)") (class "Default")
      (node (ref "P1") (pin "7") (pinfunction "7_7") (pintype "passive"))
      (node (ref "R29") (pin "1") (pinfunction "1_1") (pintype "passive"))
      (node (ref "U4") (pin "15") (pinfunction "IO,_JTAGEN_15") (pintype "bidirectional"))
    )
    (net (code "105") (name "Net-(U5-CLK1)") (class "Default")
      (node (ref "R22") (pin "2") (pinfunction "2_2") (pintype "passive"))
      (node (ref "U5") (pin "2") (pinfunction "CLK1_2") (pintype "output"))
    )
    (net (code "106") (name "Net-(U5-CLK2)") (class "Default")
      (node (ref "R23") (pin "2") (pinfunction "2_2") (pintype "passive"))
      (node (ref "U5") (pin "3") (pinfunction "CLK2_3") (pintype "output"))
    )
    (net (code "107") (name "Net-(U5-CLK4)") (class "Default")
      (node (ref "R24") (pin "2") (pinfunction "2_2") (pintype "passive"))
      (node (ref "U5") (pin "7") (pinfunction "CLK4_7") (pintype "output"))
    )
    (net (code "108") (name "Net-(U5-CLK5)") (class "Default")
      (node (ref "R25") (pin "2") (pinfunction "2_2") (pintype "passive"))
      (node (ref "U5") (pin "8") (pinfunction "CLK5_8") (pintype "output"))
    )
    (net (code "109") (name "Net-(U6-CLK1)") (class "Default")
      (node (ref "R26") (pin "2") (pinfunction "2_2") (pintype "passive"))
      (node (ref "U6") (pin "2") (pinfunction "CLK1_2") (pintype "output"))
    )
    (net (code "110") (name "Net-(U6-CLK2)") (class "Default")
      (node (ref "R30") (pin "2") (pinfunction "2_2") (pintype "passive"))
      (node (ref "U6") (pin "3") (pinfunction "CLK2_3") (pintype "output"))
    )
    (net (code "111") (name "Net-(U6-CLK4)") (class "Default")
      (node (ref "R31") (pin "2") (pinfunction "2_2") (pintype "passive"))
      (node (ref "U6") (pin "7") (pinfunction "CLK4_7") (pintype "output"))
    )
    (net (code "112") (name "Net-(U6-CLK5)") (class "Default")
      (node (ref "R32") (pin "2") (pinfunction "2_2") (pintype "passive"))
      (node (ref "U6") (pin "8") (pinfunction "CLK5_8") (pintype "output"))
    )
    (net (code "113") (name "Net-(U7-CLK1)") (class "Default")
      (node (ref "R33") (pin "2") (pinfunction "2_2") (pintype "passive"))
      (node (ref "U7") (pin "2") (pinfunction "CLK1_2") (pintype "output"))
    )
    (net (code "114") (name "Net-(U7-CLK2)") (class "Default")
      (node (ref "R34") (pin "2") (pinfunction "2_2") (pintype "passive"))
      (node (ref "U7") (pin "3") (pinfunction "CLK2_3") (pintype "output"))
    )
    (net (code "115") (name "Net-(U7-CLK4)") (class "Default")
      (node (ref "R35") (pin "2") (pinfunction "2_2") (pintype "passive"))
      (node (ref "U7") (pin "7") (pinfunction "CLK4_7") (pintype "output"))
    )
    (net (code "116") (name "Net-(U7-CLK5)") (class "Default")
      (node (ref "R36") (pin "2") (pinfunction "2_2") (pintype "passive"))
      (node (ref "U7") (pin "8") (pinfunction "CLK5_8") (pintype "output"))
    )
    (net (code "117") (name "Net-(U8-CLK1)") (class "Default")
      (node (ref "R37") (pin "2") (pinfunction "2_2") (pintype "passive"))
      (node (ref "U8") (pin "2") (pinfunction "CLK1_2") (pintype "output"))
    )
    (net (code "118") (name "Net-(U8-CLK2)") (class "Default")
      (node (ref "R38") (pin "2") (pinfunction "2_2") (pintype "passive"))
      (node (ref "U8") (pin "3") (pinfunction "CLK2_3") (pintype "output"))
    )
    (net (code "119") (name "Net-(U8-CLK4)") (class "Default")
      (node (ref "R39") (pin "2") (pinfunction "2_2") (pintype "passive"))
      (node (ref "U8") (pin "7") (pinfunction "CLK4_7") (pintype "output"))
    )
    (net (code "120") (name "Net-(U8-CLK5)") (class "Default")
      (node (ref "R40") (pin "2") (pinfunction "2_2") (pintype "passive"))
      (node (ref "U8") (pin "8") (pinfunction "CLK5_8") (pintype "output"))
    )
    (net (code "121") (name "unconnected-(P1-Pad8)") (class "Default")
      (node (ref "P1") (pin "8") (pinfunction "8_8") (pintype "passive+no_connect"))
    )
    (net (code "122") (name "unconnected-(SW2-GND-Pad5)") (class "Default")
      (node (ref "SW2") (pin "5") (pinfunction "GND_5") (pintype "passive"))
    )
    (net (code "123") (name "unconnected-(SW3-GND-Pad5)") (class "Default")
      (node (ref "SW3") (pin "5") (pinfunction "GND_5") (pintype "passive"))
    )
    (net (code "124") (name "unconnected-(U4A-IO,_CLK0n,_(DIFFIO_RX_L18n,_DIFFOUT_L18n)-Pad26)") (class "Default")
      (node (ref "U4") (pin "26") (pinfunction "IO,_CLK0n,_(DIFFIO_RX_L18n,_DIFFOUT_L18n)_26") (pintype "bidirectional"))
    )
    (net (code "125") (name "unconnected-(U4A-IO,_CLK1n,_(DIFFIO_RX_L20n,_DIFFOUT_L20n)-Pad28)") (class "Default")
      (node (ref "U4") (pin "28") (pinfunction "IO,_CLK1n,_(DIFFIO_RX_L20n,_DIFFOUT_L20n)_28") (pintype "bidirectional"))
    )
    (net (code "126") (name "unconnected-(U4A-IO,_CLK1p,_(DIFFIO_RX_L20p,_DIFFOUT_L20p)-Pad29)") (class "Default")
      (node (ref "U4") (pin "29") (pinfunction "IO,_CLK1p,_(DIFFIO_RX_L20p,_DIFFOUT_L20p)_29") (pintype "bidirectional"))
    )
    (net (code "127") (name "unconnected-(U4B-IO,_(DIFFIO_TX_RX_B1p,_DIFFOUT_B1p)-Pad39)") (class "Default")
      (node (ref "U4") (pin "39") (pinfunction "IO,_(DIFFIO_TX_RX_B1p,_DIFFOUT_B1p)_39") (pintype "bidirectional"))
    )
    (net (code "128") (name "unconnected-(U4B-IO,_(DIFFIO_TX_RX_B5n,_DIFFOUT_B5n)-Pad44)") (class "Default")
      (node (ref "U4") (pin "44") (pinfunction "IO,_(DIFFIO_TX_RX_B5n,_DIFFOUT_B5n)_44") (pintype "bidirectional"))
    )
    (net (code "129") (name "unconnected-(U4B-IO,_(DIFFIO_TX_RX_B5p,_DIFFOUT_B5p)-Pad45)") (class "Default")
      (node (ref "U4") (pin "45") (pinfunction "IO,_(DIFFIO_TX_RX_B5p,_DIFFOUT_B5p)_45") (pintype "bidirectional"))
    )
    (net (code "130") (name "unconnected-(U4B-IO,_(DIFFIO_TX_RX_B7p,_DIFFOUT_B7p)-Pad47)") (class "Default")
      (node (ref "U4") (pin "47") (pinfunction "IO,_(DIFFIO_TX_RX_B7p,_DIFFOUT_B7p)_47") (pintype "bidirectional"))
    )
    (net (code "131") (name "unconnected-(U4B-IO,_(DIFFIO_TX_RX_B12p,_DIFFOUT_B12p)-Pad56)") (class "Default")
      (node (ref "U4") (pin "56") (pinfunction "IO,_(DIFFIO_TX_RX_B12p,_DIFFOUT_B12p)_56") (pintype "bidirectional"))
    )
    (net (code "132") (name "unconnected-(U4B-IO,_VREFB3N0-Pad48)") (class "Default")
      (node (ref "U4") (pin "48") (pinfunction "IO,_VREFB3N0_48") (pintype "bidirectional"))
    )
    (net (code "133") (name "unconnected-(U4D-IO,_(DIFFIO_RX_R1n,_DIFFOUT_R1n)-Pad77)") (class "Default")
      (node (ref "U4") (pin "77") (pinfunction "IO,_(DIFFIO_RX_R1n,_DIFFOUT_R1n)_77") (pintype "bidirectional"))
    )
    (net (code "134") (name "unconnected-(U4D-IO,_(DIFFIO_RX_R1p,_DIFFOUT_R1p)-Pad75)") (class "Default")
      (node (ref "U4") (pin "75") (pinfunction "IO,_(DIFFIO_RX_R1p,_DIFFOUT_R1p)_75") (pintype "bidirectional"))
    )
    (net (code "135") (name "unconnected-(U4D-IO,_(DIFFIO_RX_R7n,_DIFFOUT_R7n)-Pad81)") (class "Default")
      (node (ref "U4") (pin "81") (pinfunction "IO,_(DIFFIO_RX_R7n,_DIFFOUT_R7n)_81") (pintype "bidirectional"))
    )
    (net (code "136") (name "unconnected-(U4D-IO,_(DIFFIO_RX_R7p,_DIFFOUT_R7p)-Pad79)") (class "Default")
      (node (ref "U4") (pin "79") (pinfunction "IO,_(DIFFIO_RX_R7p,_DIFFOUT_R7p)_79") (pintype "bidirectional"))
    )
    (net (code "137") (name "unconnected-(U4D-IO,_(DIFFIO_RX_R10p,_DIFFOUT_R10p)-Pad85)") (class "Default")
      (node (ref "U4") (pin "85") (pinfunction "IO,_(DIFFIO_RX_R10p,_DIFFOUT_R10p)_85") (pintype "bidirectional"))
    )
    (net (code "138") (name "unconnected-(U4D-IO,_(DIFFIO_RX_R11n,_DIFFOUT_R11n)-Pad86)") (class "Default")
      (node (ref "U4") (pin "86") (pinfunction "IO,_(DIFFIO_RX_R11n,_DIFFOUT_R11n)_86") (pintype "bidirectional"))
    )
    (net (code "139") (name "unconnected-(U4E-IO,_(DIFFIO_RX_R18n,_DIFFOUT_R18n)-Pad93)") (class "Default")
      (node (ref "U4") (pin "93") (pinfunction "IO,_(DIFFIO_RX_R18n,_DIFFOUT_R18n)_93") (pintype "bidirectional"))
    )
    (net (code "140") (name "unconnected-(U4E-IO,_(DIFFIO_RX_R27n,_DIFFOUT_R27n)-Pad101)") (class "Default")
      (node (ref "U4") (pin "101") (pinfunction "IO,_(DIFFIO_RX_R27n,_DIFFOUT_R27n)_101") (pintype "bidirectional"))
    )
    (net (code "141") (name "unconnected-(U4E-IO,_(DIFFIO_RX_R27p,_DIFFOUT_R27p)-Pad99)") (class "Default")
      (node (ref "U4") (pin "99") (pinfunction "IO,_(DIFFIO_RX_R27p,_DIFFOUT_R27p)_99") (pintype "bidirectional"))
    )
    (net (code "142") (name "unconnected-(U4E-IO,_(DIFFIO_RX_R33p,_DIFFOUT_R33p)-Pad105)") (class "Default")
      (node (ref "U4") (pin "105") (pinfunction "IO,_(DIFFIO_RX_R33p,_DIFFOUT_R33p)_105") (pintype "bidirectional"))
    )
    (net (code "143") (name "unconnected-(U4E-IO,_VREFB6N0-Pad97)") (class "Default")
      (node (ref "U4") (pin "97") (pinfunction "IO,_VREFB6N0_97") (pintype "bidirectional"))
    )
    (net (code "144") (name "unconnected-(U4F-IO,_(DIFFIO_RX_T1n,_DIFFOUT_T1n)-Pad111)") (class "Default")
      (node (ref "U4") (pin "111") (pinfunction "IO,_(DIFFIO_RX_T1n,_DIFFOUT_T1n)_111") (pintype "bidirectional"))
    )
    (net (code "145") (name "unconnected-(U4F-IO,_(DIFFIO_RX_T1p,_DIFFOUT_T1p)-Pad110)") (class "Default")
      (node (ref "U4") (pin "110") (pinfunction "IO,_(DIFFIO_RX_T1p,_DIFFOUT_T1p)_110") (pintype "bidirectional"))
    )
    (net (code "146") (name "unconnected-(U4F-IO,_(DIFFIO_RX_T10p,_DIFFOUT_T10p)-Pad118)") (class "Default")
      (node (ref "U4") (pin "118") (pinfunction "IO,_(DIFFIO_RX_T10p,_DIFFOUT_T10p)_118") (pintype "bidirectional"))
    )
    (net (code "147") (name "unconnected-(U4F-IO,_VREFB7N0-Pad112)") (class "Default")
      (node (ref "U4") (pin "112") (pinfunction "IO,_VREFB7N0_112") (pintype "bidirectional"))
    )
    (net (code "148") (name "unconnected-(U4F-IO-Pad113)") (class "Default")
      (node (ref "U4") (pin "113") (pinfunction "IO_113") (pintype "bidirectional"))
    )
    (net (code "149") (name "unconnected-(U4F-IO-Pad114)") (class "Default")
      (node (ref "U4") (pin "114") (pinfunction "IO_114") (pintype "bidirectional"))
    )
    (net (code "150") (name "unconnected-(U4G-IO,_(DIFFIO_RX_T16p,_DIFFOUT_T16p)-Pad120)") (class "Default")
      (node (ref "U4") (pin "120") (pinfunction "IO,_(DIFFIO_RX_T16p,_DIFFOUT_T16p)_120") (pintype "bidirectional"))
    )
    (net (code "151") (name "unconnected-(U4G-IO,_(DIFFIO_RX_T19n,_DIFFOUT_T19n)-Pad127)") (class "Default")
      (node (ref "U4") (pin "127") (pinfunction "IO,_(DIFFIO_RX_T19n,_DIFFOUT_T19n)_127") (pintype "bidirectional"))
    )
    (net (code "152") (name "unconnected-(U4G-IO,_(DIFFIO_RX_T19p,_DIFFOUT_T19p)-Pad124)") (class "Default")
      (node (ref "U4") (pin "124") (pinfunction "IO,_(DIFFIO_RX_T19p,_DIFFOUT_T19p)_124") (pintype "bidirectional"))
    )
    (net (code "153") (name "unconnected-(U4G-IO,_(DIFFIO_RX_T20n,_DIFFOUT_T20n)-Pad131)") (class "Default")
      (node (ref "U4") (pin "131") (pinfunction "IO,_(DIFFIO_RX_T20n,_DIFFOUT_T20n)_131") (pintype "bidirectional"))
    )
    (net (code "154") (name "unconnected-(U4G-IO,_(DIFFIO_RX_T20p,_DIFFOUT_T20p)-Pad130)") (class "Default")
      (node (ref "U4") (pin "130") (pinfunction "IO,_(DIFFIO_RX_T20p,_DIFFOUT_T20p)_130") (pintype "bidirectional"))
    )
    (net (code "155") (name "unconnected-(U4G-IO,_(DIFFIO_RX_T22p,_DIFFOUT_T22p)-Pad132)") (class "Default")
      (node (ref "U4") (pin "132") (pinfunction "IO,_(DIFFIO_RX_T22p,_DIFFOUT_T22p)_132") (pintype "bidirectional"))
    )
    (net (code "156") (name "unconnected-(U4G-IO,_CONFIG_SEL-Pad126)") (class "Default")
      (node (ref "U4") (pin "126") (pinfunction "IO,_CONFIG_SEL_126") (pintype "bidirectional"))
    )
    (net (code "157") (name "unconnected-(U4G-IO,_CRC_ERROR,_(DIFFIO_RX_T22n,_DIFFOUT_T22n)-Pad134)") (class "Default")
      (node (ref "U4") (pin "134") (pinfunction "IO,_CRC_ERROR,_(DIFFIO_RX_T22n,_DIFFOUT_T22n)_134") (pintype "bidirectional"))
    )
    (net (code "158") (name "unconnected-(U4G-IO,_VREFB8N0-Pad123)") (class "Default")
      (node (ref "U4") (pin "123") (pinfunction "IO,_VREFB8N0_123") (pintype "bidirectional"))
    )
    (net (code "159") (name "unconnected-(U4H-IO,_ADC1IN4,_(DIFFIO_RX_L3p,_DIFFOUT_L3p)-Pad10)") (class "Default")
      (node (ref "U4") (pin "10") (pinfunction "IO,_ADC1IN4,_(DIFFIO_RX_L3p,_DIFFOUT_L3p)_10") (pintype "bidirectional"))
    )
    (net (code "160") (name "unconnected-(U4H-IO,_ADC1IN6,_(DIFFIO_RX_L5p,_DIFFOUT_L5p)-Pad12)") (class "Default")
      (node (ref "U4") (pin "12") (pinfunction "IO,_ADC1IN6,_(DIFFIO_RX_L5p,_DIFFOUT_L5p)_12") (pintype "bidirectional"))
    )
    (net (code "161") (name "unconnected-(U4H-IO,_ADC1IN7,_(DIFFIO_RX_L7n,_DIFFOUT_L7n)-Pad13)") (class "Default")
      (node (ref "U4") (pin "13") (pinfunction "IO,_ADC1IN7,_(DIFFIO_RX_L7n,_DIFFOUT_L7n)_13") (pintype "bidirectional"))
    )
    (net (code "162") (name "unconnected-(U4I-IO,_(DIFFIO_RX_L14n,_DIFFOUT_L14n)-Pad21)") (class "Default")
      (node (ref "U4") (pin "21") (pinfunction "IO,_(DIFFIO_RX_L14n,_DIFFOUT_L14n)_21") (pintype "bidirectional"))
    )
    (net (code "163") (name "unconnected-(U4I-IO,_(DIFFIO_RX_L14p,_DIFFOUT_L14p)-Pad22)") (class "Default")
      (node (ref "U4") (pin "22") (pinfunction "IO,_(DIFFIO_RX_L14p,_DIFFOUT_L14p)_22") (pintype "bidirectional"))
    )
    (net (code "164") (name "unconnected-(U4I-IO,_(DIFFIO_RX_L16n,_DIFFOUT_L16n)-Pad24)") (class "Default")
      (node (ref "U4") (pin "24") (pinfunction "IO,_(DIFFIO_RX_L16n,_DIFFOUT_L16n)_24") (pintype "bidirectional"))
    )
    (net (code "165") (name "unconnected-(U4I-IO,_VREFB1N0-Pad17)") (class "Default")
      (node (ref "U4") (pin "17") (pinfunction "IO,_VREFB1N0_17") (pintype "bidirectional"))
    )
    (net (code "166") (name "unconnected-(U5-CLK3-Pad5)") (class "Default")
      (node (ref "U5") (pin "5") (pinfunction "CLK3_5") (pintype "output"))
    )
    (net (code "167") (name "unconnected-(U6-CLK3-Pad5)") (class "Default")
      (node (ref "U6") (pin "5") (pinfunction "CLK3_5") (pintype "output+no_connect"))
    )
    (net (code "168") (name "unconnected-(U7-CLK3-Pad5)") (class "Default")
      (node (ref "U7") (pin "5") (pinfunction "CLK3_5") (pintype "output+no_connect"))
    )
    (net (code "169") (name "unconnected-(U8-CLK3-Pad5)") (class "Default")
      (node (ref "U8") (pin "5") (pinfunction "CLK3_5") (pintype "output+no_connect"))
    )
    (net (code "170") (name "unconnected-(Y1-STAND-BY-Pad1)") (class "Default")
      (node (ref "Y1") (pin "1") (pinfunction "STAND-BY_1") (pintype "input+no_connect"))
    )
  )
)
